# Button_EasyEDA_PRO.net
KiCad netlist of a schematic drawn in EasyEDA Pro
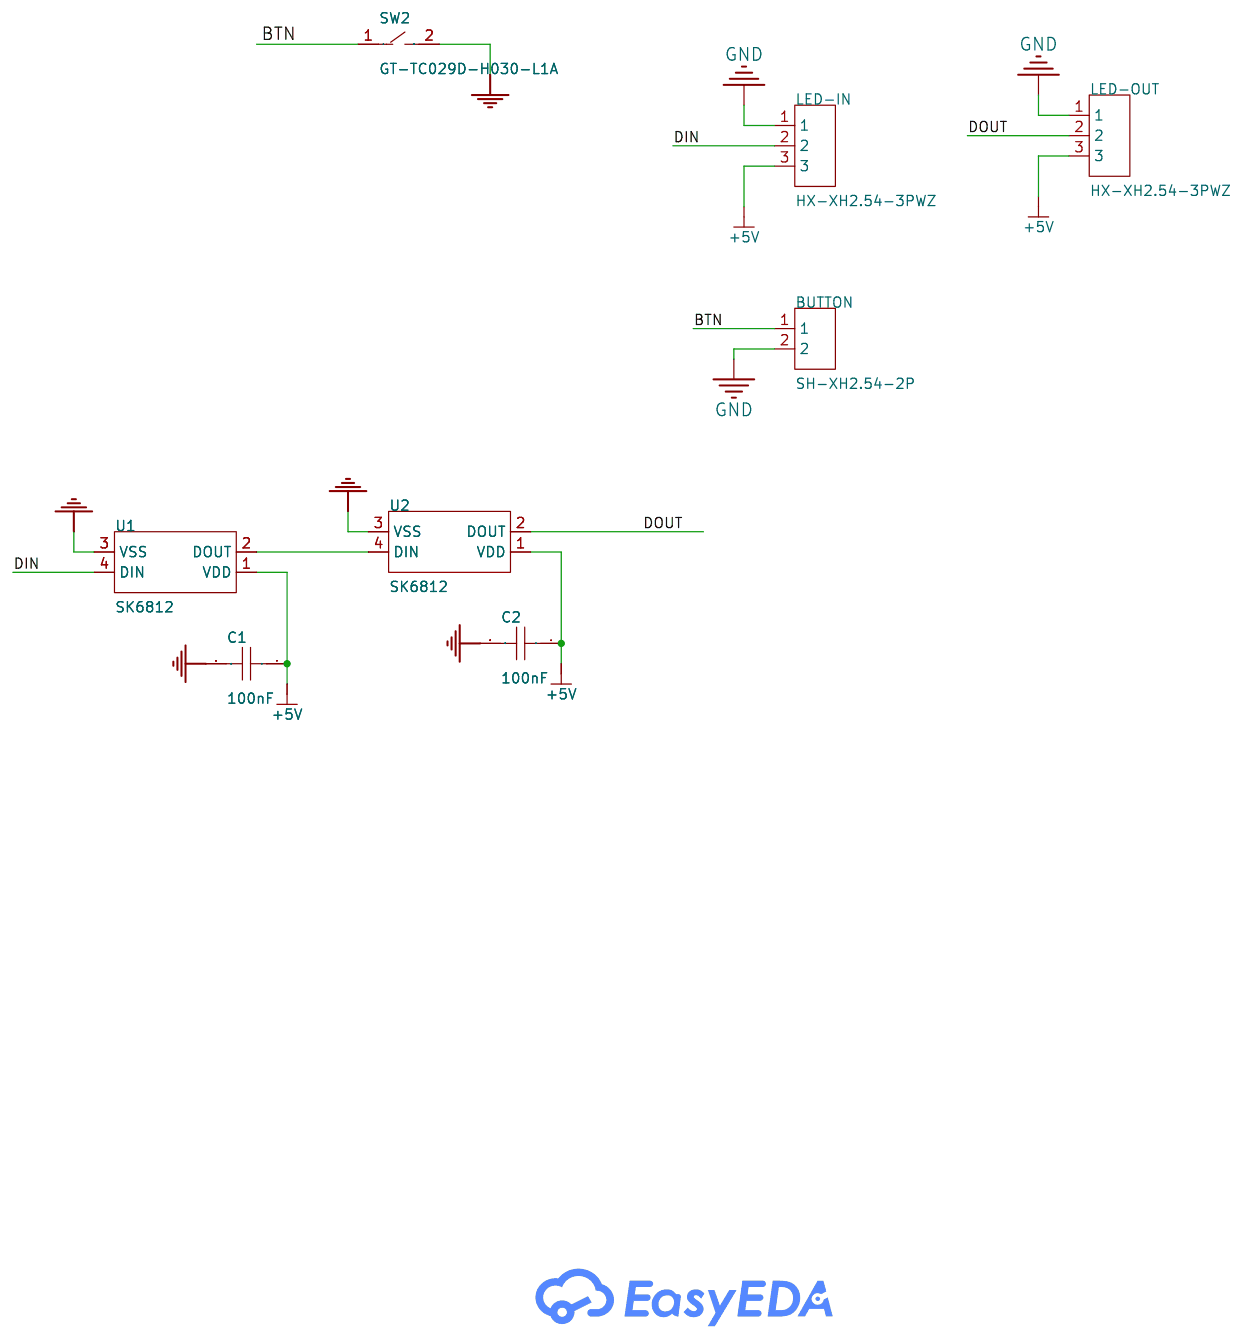
[diagram p0: schematic sheet]

(export (version "E")
  (design (tool "Eeschema 10.0.6"))
  (components
    (comp (ref "BUTTON")
      (value "SH-XH2.54-2P")
      (footprint "easyedapro:CONN-TH_2P-P2.50-XH2.54-2P")
      (fields (field (name "Manufacturer") "深海电子"))
      (libsource (lib "easyedapro") (part "SH-XH2.54-2P"))
    )
    (comp (ref "C1")
      (value "100nF")
      (footprint "easyedapro:C0603")
      (libsource (lib "easyedapro") (part "CAP"))
    )
    (comp (ref "C2")
      (value "100nF")
      (footprint "easyedapro:C0603")
      (libsource (lib "easyedapro") (part "CAP"))
    )
    (comp (ref "LED-IN")
      (value "HX-XH2.54-3PWZ")
      (footprint "easyedapro:CONN-TH_3P-P2.50_BX-HA2.54-3PWZ")
      (fields (field (name "Manufacturer") "hanxia(韩下)"))
      (libsource (lib "easyedapro") (part "HX-XH2.54-3PWZ"))
    )
    (comp (ref "LED-OUT")
      (value "HX-XH2.54-3PWZ")
      (footprint "easyedapro:CONN-TH_3P-P2.50_BX-HA2.54-3PWZ")
      (fields (field (name "Manufacturer") "hanxia(韩下)"))
      (libsource (lib "easyedapro") (part "HX-XH2.54-3PWZ"))
    )
    (comp (ref "SW2")
      (value "GT-TC029D-H030-L1A")
      (footprint "easyedapro:SW-SMD_GT-TC029D-H030-L1A")
      (fields (field (name "Manufacturer") "G-Switch(品赞)"))
      (libsource (lib "easyedapro") (part "GT-TC029D-H030-L1A"))
    )
    (comp (ref "U1")
      (value "SK6812")
      (footprint "easyedapro:LED-SMD_4P-L5.0-W5.0-LS5.4-TL-1")
      (fields (field (name "Manufacturer") "欧思科光电"))
      (libsource (lib "easyedapro") (part "SK6812_C5378720"))
    )
    (comp (ref "U2")
      (value "SK6812")
      (footprint "easyedapro:LED-SMD_4P-L5.0-W5.0-LS5.4-TL-1")
      (fields (field (name "Manufacturer") "欧思科光电"))
      (libsource (lib "easyedapro") (part "SK6812_C5378720"))
    )
  )
  (nets
    (net (code "1") (name "+5V") (class "Default")
      (node (ref "C1") (pin "1") (pinfunction "1_1") (pintype "input"))
      (node (ref "C2") (pin "1") (pinfunction "1_1") (pintype "input"))
      (node (ref "LED-IN") (pin "3") (pinfunction "3_3") (pintype "unspecified"))
      (node (ref "LED-OUT") (pin "3") (pinfunction "3_3") (pintype "unspecified"))
      (node (ref "U1") (pin "1") (pinfunction "VDD_1") (pintype "unspecified"))
      (node (ref "U2") (pin "1") (pinfunction "VDD_1") (pintype "unspecified"))
    )
    (net (code "2") (name "/BTN") (class "Default")
      (node (ref "BUTTON") (pin "1") (pinfunction "1_1") (pintype "unspecified"))
      (node (ref "SW2") (pin "1") (pinfunction "1_1") (pintype "unspecified"))
    )
    (net (code "3") (name "/DIN") (class "Default")
      (node (ref "LED-IN") (pin "2") (pinfunction "2_2") (pintype "unspecified"))
      (node (ref "U1") (pin "4") (pinfunction "DIN_4") (pintype "unspecified"))
    )
    (net (code "4") (name "/DOUT") (class "Default")
      (node (ref "LED-OUT") (pin "2") (pinfunction "2_2") (pintype "unspecified"))
      (node (ref "U2") (pin "2") (pinfunction "DOUT_2") (pintype "unspecified"))
    )
    (net (code "5") (name "GND") (class "Default")
      (node (ref "BUTTON") (pin "2") (pinfunction "2_2") (pintype "unspecified"))
      (node (ref "C1") (pin "2") (pinfunction "2_2") (pintype "input"))
      (node (ref "C2") (pin "2") (pinfunction "2_2") (pintype "input"))
      (node (ref "LED-IN") (pin "1") (pinfunction "1_1") (pintype "unspecified"))
      (node (ref "LED-OUT") (pin "1") (pinfunction "1_1") (pintype "unspecified"))
      (node (ref "SW2") (pin "2") (pinfunction "2_2") (pintype "unspecified"))
      (node (ref "U1") (pin "3") (pinfunction "VSS_3") (pintype "unspecified"))
      (node (ref "U2") (pin "3") (pinfunction "VSS_3") (pintype "unspecified"))
    )
    (net (code "6") (name "Net-(U1-DOUT)") (class "Default")
      (node (ref "U1") (pin "2") (pinfunction "DOUT_2") (pintype "unspecified"))
      (node (ref "U2") (pin "4") (pinfunction "DIN_4") (pintype "unspecified"))
    )
  )
)
